# SPE_router_eth.net
KiCad netlist of a schematic drawn in Altium Designer
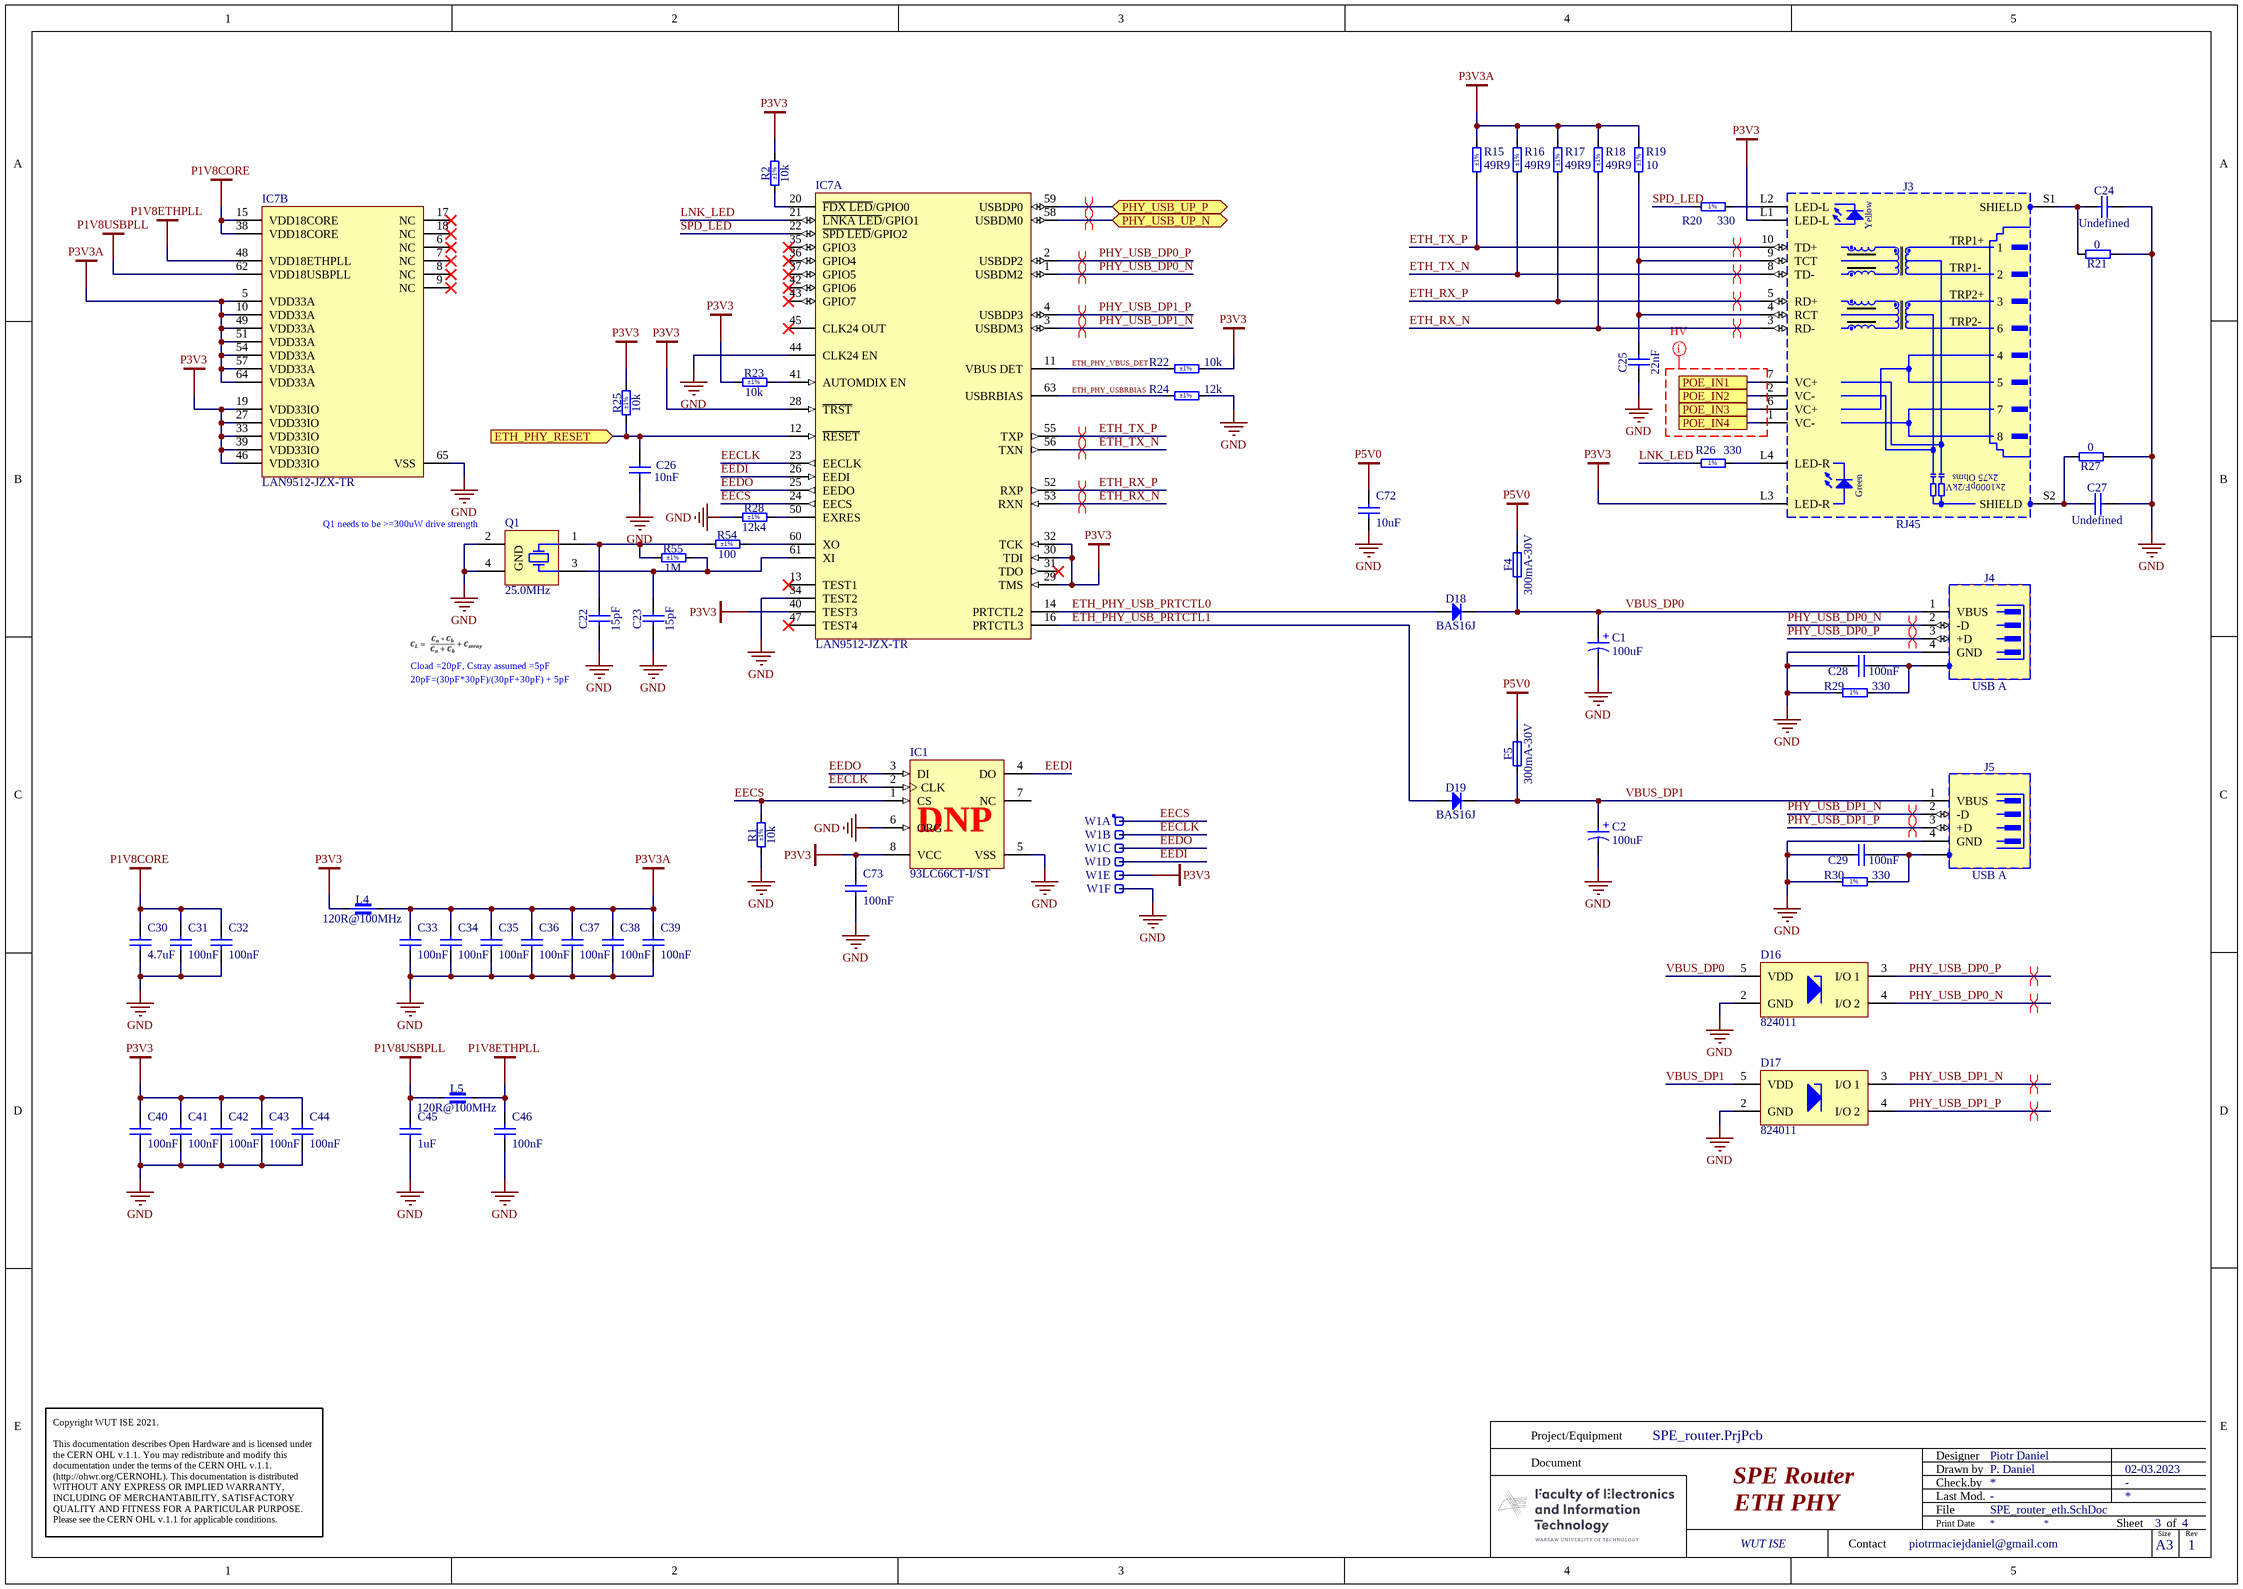
[diagram p0: SPE_router_eth.SchDoc]

(export (version "E")
  (design (tool "Eeschema 10.0.6"))
  (components
    (comp (ref "C1")
      (value "100uF")
      (footprint "WCAP-ASLU_D5H5.5")
      (description "865090142005 Electrolytic capacitor; SMD; 100uF; 6.3V; 20%; 85deg.C; 5.0x5.5")
      (fields (field (name "TOLERANCE") "20%") (field (name "MANUFACTURER") "Wurth Elektronik"))
      (libsource (lib "Altium Content Vault") (part "Capacitor_Polarized"))
    )
    (comp (ref "C2")
      (value "100uF")
      (footprint "WCAP-ASLU_D5H5.5")
      (description "865090142005 Electrolytic capacitor; SMD; 100uF; 6.3V; 20%; 85deg.C; 5.0x5.5")
      (fields (field (name "TOLERANCE") "20%") (field (name "MANUFACTURER") "Wurth Elektronik"))
      (libsource (lib "Altium Content Vault") (part "Capacitor_Polarized"))
    )
    (comp (ref "C22")
      (value "15pF")
      (footprint "CAPC1005X55N")
      (description "Non-polarised capacitor")
      (fields
        (field (name "PART NUMBER") "CC0402_15PF_50V_5%_C0G")
        (field (name "VOLTAGE") "50V")
        (field (name "AUTHOR") "CERN DEM JLC")
      )
      (libsource (lib "Capacitors") (part "Capacitor - non polarized"))
    )
    (comp (ref "C23")
      (value "15pF")
      (footprint "CAPC1005X55N")
      (description "Non-polarised capacitor")
      (fields
        (field (name "PART NUMBER") "CC0402_15PF_50V_5%_C0G")
        (field (name "VOLTAGE") "50V")
        (field (name "AUTHOR") "CERN DEM JLC")
      )
      (libsource (lib "Capacitors") (part "Capacitor - non polarized"))
    )
    (comp (ref "C24")
      (value "Undefined")
      (footprint "CAPC2012X135N")
      (description "Non-polarised capacitor")
      (fields (field (name "PART NUMBER") "CC0805_NO-VALUE") (field (name "AUTHOR") "CERN DEM JLC"))
      (libsource (lib "Capacitors") (part "Capacitor - non polarized"))
    )
    (comp (ref "C25")
      (value "22nF")
      (footprint "CAPC2012X145N")
      (description "Non-polarised capacitor")
      (fields
        (field (name "PART NUMBER") "CC0805_22NF_50V_10%_X7R_YUDEN_UMJ212BB7223KGHT")
        (field (name "VOLTAGE") "50V")
        (field (name "AUTHOR") "CERN DEM JLC")
      )
      (libsource (lib "Capacitors") (part "Capacitor - non polarized"))
    )
    (comp (ref "C26")
      (value "10nF")
      (footprint "CAPC1005X55N")
      (description "Non-polarised capacitor")
      (fields
        (field (name "PART NUMBER") "CC0402_10NF_16V_10%_X7R")
        (field (name "VOLTAGE") "16V")
        (field (name "AUTHOR") "CERN DEM JLC")
      )
      (libsource (lib "Capacitors") (part "Capacitor - non polarized"))
    )
    (comp (ref "C27")
      (value "Undefined")
      (footprint "CAPC2012X135N")
      (description "Non-polarised capacitor")
      (fields (field (name "PART NUMBER") "CC0805_NO-VALUE") (field (name "AUTHOR") "CERN DEM JLC"))
      (libsource (lib "Capacitors") (part "Capacitor - non polarized"))
    )
    (comp (ref "C28")
      (value "100nF")
      (footprint "CAPC1005X55N")
      (description "Non-polarised capacitor")
      (fields
        (field (name "PART NUMBER") "CC0402_100NF_16V_10%_X7R")
        (field (name "VOLTAGE") "16V")
        (field (name "AUTHOR") "CERN DEM JLC")
      )
      (libsource (lib "Capacitors") (part "Capacitor - non polarized"))
    )
    (comp (ref "C29")
      (value "100nF")
      (footprint "CAPC1005X55N")
      (description "Non-polarised capacitor")
      (fields
        (field (name "PART NUMBER") "CC0402_100NF_16V_10%_X7R")
        (field (name "VOLTAGE") "16V")
        (field (name "AUTHOR") "CERN DEM JLC")
      )
      (libsource (lib "Capacitors") (part "Capacitor - non polarized"))
    )
    (comp (ref "C30")
      (value "4.7uF")
      (footprint "CAPC1709X95N")
      (description "Non-polarised capacitor")
      (fields
        (field (name "PART NUMBER") "CC0603_4.7UF_16V_10%_X5R")
        (field (name "VOLTAGE") "16V")
        (field (name "AUTHOR") "CERN DEM JLC")
      )
      (libsource (lib "Capacitors") (part "Capacitor - non polarized"))
    )
    (comp (ref "C31")
      (value "100nF")
      (footprint "CAPC1005X55N")
      (description "Non-polarised capacitor")
      (fields
        (field (name "PART NUMBER") "CC0402_100NF_16V_10%_X7R")
        (field (name "VOLTAGE") "16V")
        (field (name "AUTHOR") "CERN DEM JLC")
      )
      (libsource (lib "Capacitors") (part "Capacitor - non polarized"))
    )
    (comp (ref "C32")
      (value "100nF")
      (footprint "CAPC1005X55N")
      (description "Non-polarised capacitor")
      (fields
        (field (name "PART NUMBER") "CC0402_100NF_16V_10%_X7R")
        (field (name "VOLTAGE") "16V")
        (field (name "AUTHOR") "CERN DEM JLC")
      )
      (libsource (lib "Capacitors") (part "Capacitor - non polarized"))
    )
    (comp (ref "C33")
      (value "100nF")
      (footprint "CAPC1005X55N")
      (description "Non-polarised capacitor")
      (fields
        (field (name "PART NUMBER") "CC0402_100NF_16V_10%_X7R")
        (field (name "VOLTAGE") "16V")
        (field (name "AUTHOR") "CERN DEM JLC")
      )
      (libsource (lib "Capacitors") (part "Capacitor - non polarized"))
    )
    (comp (ref "C34")
      (value "100nF")
      (footprint "CAPC1005X55N")
      (description "Non-polarised capacitor")
      (fields
        (field (name "PART NUMBER") "CC0402_100NF_16V_10%_X7R")
        (field (name "VOLTAGE") "16V")
        (field (name "AUTHOR") "CERN DEM JLC")
      )
      (libsource (lib "Capacitors") (part "Capacitor - non polarized"))
    )
    (comp (ref "C35")
      (value "100nF")
      (footprint "CAPC1005X55N")
      (description "Non-polarised capacitor")
      (fields
        (field (name "PART NUMBER") "CC0402_100NF_16V_10%_X7R")
        (field (name "VOLTAGE") "16V")
        (field (name "AUTHOR") "CERN DEM JLC")
      )
      (libsource (lib "Capacitors") (part "Capacitor - non polarized"))
    )
    (comp (ref "C36")
      (value "100nF")
      (footprint "CAPC1005X55N")
      (description "Non-polarised capacitor")
      (fields
        (field (name "PART NUMBER") "CC0402_100NF_16V_10%_X7R")
        (field (name "VOLTAGE") "16V")
        (field (name "AUTHOR") "CERN DEM JLC")
      )
      (libsource (lib "Capacitors") (part "Capacitor - non polarized"))
    )
    (comp (ref "C37")
      (value "100nF")
      (footprint "CAPC1005X55N")
      (description "Non-polarised capacitor")
      (fields
        (field (name "PART NUMBER") "CC0402_100NF_16V_10%_X7R")
        (field (name "VOLTAGE") "16V")
        (field (name "AUTHOR") "CERN DEM JLC")
      )
      (libsource (lib "Capacitors") (part "Capacitor - non polarized"))
    )
    (comp (ref "C38")
      (value "100nF")
      (footprint "CAPC1005X55N")
      (description "Non-polarised capacitor")
      (fields
        (field (name "PART NUMBER") "CC0402_100NF_16V_10%_X7R")
        (field (name "VOLTAGE") "16V")
        (field (name "AUTHOR") "CERN DEM JLC")
      )
      (libsource (lib "Capacitors") (part "Capacitor - non polarized"))
    )
    (comp (ref "C39")
      (value "100nF")
      (footprint "CAPC1005X55N")
      (description "Non-polarised capacitor")
      (fields
        (field (name "PART NUMBER") "CC0402_100NF_16V_10%_X7R")
        (field (name "VOLTAGE") "16V")
        (field (name "AUTHOR") "CERN DEM JLC")
      )
      (libsource (lib "Capacitors") (part "Capacitor - non polarized"))
    )
    (comp (ref "C40")
      (value "100nF")
      (footprint "CAPC1005X55N")
      (description "Non-polarised capacitor")
      (fields
        (field (name "PART NUMBER") "CC0402_100NF_16V_10%_X7R")
        (field (name "VOLTAGE") "16V")
        (field (name "AUTHOR") "CERN DEM JLC")
      )
      (libsource (lib "Capacitors") (part "Capacitor - non polarized"))
    )
    (comp (ref "C41")
      (value "100nF")
      (footprint "CAPC1005X55N")
      (description "Non-polarised capacitor")
      (fields
        (field (name "PART NUMBER") "CC0402_100NF_16V_10%_X7R")
        (field (name "VOLTAGE") "16V")
        (field (name "AUTHOR") "CERN DEM JLC")
      )
      (libsource (lib "Capacitors") (part "Capacitor - non polarized"))
    )
    (comp (ref "C42")
      (value "100nF")
      (footprint "CAPC1005X55N")
      (description "Non-polarised capacitor")
      (fields
        (field (name "PART NUMBER") "CC0402_100NF_16V_10%_X7R")
        (field (name "VOLTAGE") "16V")
        (field (name "AUTHOR") "CERN DEM JLC")
      )
      (libsource (lib "Capacitors") (part "Capacitor - non polarized"))
    )
    (comp (ref "C43")
      (value "100nF")
      (footprint "CAPC1005X55N")
      (description "Non-polarised capacitor")
      (fields
        (field (name "PART NUMBER") "CC0402_100NF_16V_10%_X7R")
        (field (name "VOLTAGE") "16V")
        (field (name "AUTHOR") "CERN DEM JLC")
      )
      (libsource (lib "Capacitors") (part "Capacitor - non polarized"))
    )
    (comp (ref "C44")
      (value "100nF")
      (footprint "CAPC1005X55N")
      (description "Non-polarised capacitor")
      (fields
        (field (name "PART NUMBER") "CC0402_100NF_16V_10%_X7R")
        (field (name "VOLTAGE") "16V")
        (field (name "AUTHOR") "CERN DEM JLC")
      )
      (libsource (lib "Capacitors") (part "Capacitor - non polarized"))
    )
    (comp (ref "C45")
      (value "1uF")
      (footprint "CAPC1005X55N")
      (description "Non-polarised capacitor")
      (fields
        (field (name "PART NUMBER") "CC0402_1UF_16V_10%_X5R")
        (field (name "VOLTAGE") "16V")
        (field (name "AUTHOR") "CERN DEM JLC")
      )
      (libsource (lib "Capacitors") (part "Capacitor - non polarized"))
    )
    (comp (ref "C46")
      (value "100nF")
      (footprint "CAPC1005X55N")
      (description "Non-polarised capacitor")
      (fields
        (field (name "PART NUMBER") "CC0402_100NF_16V_10%_X7R")
        (field (name "VOLTAGE") "16V")
        (field (name "AUTHOR") "CERN DEM JLC")
      )
      (libsource (lib "Capacitors") (part "Capacitor - non polarized"))
    )
    (comp (ref "C72")
      (value "10uF")
      (footprint "CAPC3216X180N")
      (description "Non-polarised capacitor")
      (fields
        (field (name "PART NUMBER") "CC1206_10UF_25V_10%_X7R")
        (field (name "VOLTAGE") "25V")
        (field (name "AUTHOR") "CERN DEM JLC")
      )
      (libsource (lib "Capacitors") (part "Capacitor - non polarized"))
    )
    (comp (ref "C73")
      (value "100nF")
      (footprint "CAPC1005X55N")
      (description "Non-polarised capacitor")
      (fields
        (field (name "PART NUMBER") "CC0402_100NF_16V_10%_X7R")
        (field (name "VOLTAGE") "16V")
        (field (name "AUTHOR") "CERN DEM JLC")
      )
      (libsource (lib "Capacitors") (part "Capacitor - non polarized"))
    )
    (comp (ref "D16")
      (value "824011")
      (footprint "WE-TVS_SOT23-5L")
      (libsource (lib "Altium Content Vault") (part "Diode_2+1 Channel_Unidirectional - 824011"))
    )
    (comp (ref "D17")
      (value "824011")
      (footprint "WE-TVS_SOT23-5L")
      (libsource (lib "Altium Content Vault") (part "Diode_2+1 Channel_Unidirectional - 824011"))
    )
    (comp (ref "D18")
      (value "BAS16J")
      (footprint "SODFL2513X80N")
      (description "Diode")
      (fields
        (field (name "VOLTAGE") "100V")
        (field (name "POWER") "250mA")
        (field (name "AUTHOR") "CERN DEM BC")
      )
      (libsource (lib "ICs And Semiconductors") (part "Diode"))
    )
    (comp (ref "D19")
      (value "BAS16J")
      (footprint "SODFL2513X80N")
      (description "Diode")
      (fields
        (field (name "VOLTAGE") "100V")
        (field (name "POWER") "250mA")
        (field (name "AUTHOR") "CERN DEM BC")
      )
      (libsource (lib "ICs And Semiconductors") (part "Diode"))
    )
    (comp (ref "F4")
      (value "300mA-30V")
      (footprint "FUSR_BOURNS_MF-MSMF_STYLE1(H110)")
      (description "Fuse")
      (fields
        (field (name "PART NUMBER") "FUSR_BOURNS_MF-MSMF030-2")
        (field (name "MANUFACTURER") "BOURNS")
        (field (name "AUTHOR") "CERN DEM JLC")
      )
      (libsource (lib "Eletro-mechanical") (part "Fuse"))
    )
    (comp (ref "F5")
      (value "300mA-30V")
      (footprint "FUSR_BOURNS_MF-MSMF_STYLE1(H110)")
      (description "Fuse")
      (fields
        (field (name "PART NUMBER") "FUSR_BOURNS_MF-MSMF030-2")
        (field (name "MANUFACTURER") "BOURNS")
        (field (name "AUTHOR") "CERN DEM JLC")
      )
      (libsource (lib "Eletro-mechanical") (part "Fuse"))
    )
    (comp (ref "IC1")
      (value "93LC66CT-I/ST")
      (footprint "TSSOP-ST8_M")
      (libsource (lib "Altium Content Vault") (part "MEM-SEEPROM-93AA46C-P-8"))
    )
    (comp (ref "IC7")
      (value "LAN9512-JZX-TR")
      (footprint "FP-LAN9512-JZX-TR-IPC_B")
      (description "USB 2.0 to 10/100 Ethernet Controllers with 2-port USB2.0 Hub, 64 QFN 9x9x0.9mm")
      (fields (field (name "MANUFACTURER") "Microchip"))
      (libsource (lib "SPE_router_lib") (part "LAN9512-JZX-TR"))
    )
    (comp (ref "J3")
      (value "RJ45")
      (footprint "ABRACON_ARJM11C7-114-BA-EW2")
      (description "MagJack 10/100BaseT, PoE+, 1X1, OG/Y, -40 to 85*C, Tab Up, RoHS")
      (fields
        (field (name "PART NUMBER") "ARJM11C7-114-BA-EW2")
        (field (name "MANUFACTURER") "Abracon")
        (field (name "AUTHOR") "GK")
      )
      (libsource (lib "SPE_router_lib") (part "CON_ETH_POE_ARJM11C7"))
    )
    (comp (ref "J4")
      (value "USB A")
      (footprint "AMPHENOL_73725-0110")
      (description "4 Pin + 1 Shield USB Receptacle")
      (fields
        (field (name "PART NUMBER") "AMPHENOL_73725-0110BLF")
        (field (name "MANUFACTURER") "AMPHENOL")
        (field (name "AUTHOR") "CERN DEM BC")
      )
      (libsource (lib "Connectors") (part "Connector USB 4 Pin + 1Shield"))
    )
    (comp (ref "J5")
      (value "USB A")
      (footprint "AMPHENOL_73725-0110")
      (description "4 Pin + 1 Shield USB Receptacle")
      (fields
        (field (name "PART NUMBER") "AMPHENOL_73725-0110BLF")
        (field (name "MANUFACTURER") "AMPHENOL")
        (field (name "AUTHOR") "CERN DEM BC")
      )
      (libsource (lib "Connectors") (part "Connector USB 4 Pin + 1Shield"))
    )
    (comp (ref "L4")
      (value "120R@100MHz")
      (footprint "INDC1608X95N")
      (fields
        (field (name "PART NUMBER") "IND0603_MURATA_BLM18PG121SN1D")
        (field (name "POWER") "2A")
        (field (name "MANUFACTURER") "MURATA")
        (field (name "AUTHOR") "CERN DEM BC")
      )
      (libsource (lib "Inductors & Transformers") (part "Ferrite Bead"))
    )
    (comp (ref "L5")
      (value "120R@100MHz")
      (footprint "INDC1608X95N")
      (fields
        (field (name "PART NUMBER") "IND0603_MURATA_BLM18PG121SN1D")
        (field (name "POWER") "2A")
        (field (name "MANUFACTURER") "MURATA")
        (field (name "AUTHOR") "CERN DEM BC")
      )
      (libsource (lib "Inductors & Transformers") (part "Ferrite Bead"))
    )
    (comp (ref "Q1")
      (value "25.0MHz")
      (footprint "XTAL_KYOCERA_CX3225SB")
      (description "Crystal 25 Mhz 12PF SMD")
      (fields
        (field (name "MANUFACTURER") "ECS International")
        (field (name "MANUFACTURER PART NUMBER") "ECS-250-12-33B-CWY-TR3")
      )
      (libsource (lib "SPE_router_lib") (part "ECS-250-12-33B-CWY-TR3"))
    )
    (comp (ref "R1")
      (value "10k")
      (footprint "RESC1005X40N")
      (description "Resistor - 1%")
      (fields
        (field (name "TOLERANCE") "±1%")
        (field (name "PART NUMBER") "R0402_10K_1%_0.0625W_100PPM")
        (field (name "POWER") "0.0625W")
        (field (name "AUTHOR") "CERN DEM JLC")
      )
      (libsource (lib "Resistors") (part "Resistor - 1%"))
    )
    (comp (ref "R2")
      (value "10k")
      (footprint "RESC1005X40N")
      (description "Resistor - 1%")
      (fields
        (field (name "TOLERANCE") "±1%")
        (field (name "PART NUMBER") "R0402_10K_1%_0.0625W_100PPM")
        (field (name "POWER") "0.0625W")
        (field (name "AUTHOR") "CERN DEM JLC")
      )
      (libsource (lib "Resistors") (part "Resistor - 1%"))
    )
    (comp (ref "R15")
      (value "49R9")
      (footprint "RESC1005X40N")
      (description "Resistor - 1%")
      (fields
        (field (name "TOLERANCE") "±1%")
        (field (name "PART NUMBER") "R0402_49R9_1%_0.0625W_100PPM")
        (field (name "POWER") "0.0625W")
        (field (name "AUTHOR") "CERN DEM JLC")
      )
      (libsource (lib "Resistors") (part "Resistor - 1%"))
    )
    (comp (ref "R16")
      (value "49R9")
      (footprint "RESC1005X40N")
      (description "Resistor - 1%")
      (fields
        (field (name "TOLERANCE") "±1%")
        (field (name "PART NUMBER") "R0402_49R9_1%_0.0625W_100PPM")
        (field (name "POWER") "0.0625W")
        (field (name "AUTHOR") "CERN DEM JLC")
      )
      (libsource (lib "Resistors") (part "Resistor - 1%"))
    )
    (comp (ref "R17")
      (value "49R9")
      (footprint "RESC1005X40N")
      (description "Resistor - 1%")
      (fields
        (field (name "TOLERANCE") "±1%")
        (field (name "PART NUMBER") "R0402_49R9_1%_0.0625W_100PPM")
        (field (name "POWER") "0.0625W")
        (field (name "AUTHOR") "CERN DEM JLC")
      )
      (libsource (lib "Resistors") (part "Resistor - 1%"))
    )
    (comp (ref "R18")
      (value "49R9")
      (footprint "RESC1005X40N")
      (description "Resistor - 1%")
      (fields
        (field (name "TOLERANCE") "±1%")
        (field (name "PART NUMBER") "R0402_49R9_1%_0.0625W_100PPM")
        (field (name "POWER") "0.0625W")
        (field (name "AUTHOR") "CERN DEM JLC")
      )
      (libsource (lib "Resistors") (part "Resistor - 1%"))
    )
    (comp (ref "R19")
      (value "10")
      (footprint "RESC1005X40N")
      (description "Resistor - 1%")
      (fields
        (field (name "TOLERANCE") "±1%")
        (field (name "PART NUMBER") "R0402_10R_1%_0.0625W_200PPM")
        (field (name "POWER") "0.0625W")
        (field (name "AUTHOR") "CERN DEM JLC")
      )
      (libsource (lib "Resistors") (part "Resistor - 1%"))
    )
    (comp (ref "R20")
      (value "330")
      (footprint "RESC1005X40N")
      (description "Resistor - 1%")
      (fields
        (field (name "PART NUMBER") "R0402_330R_1%_0.0625W_100PPM")
        (field (name "POWER") "0.0625W")
        (field (name "AUTHOR") "CERN DEM JLC")
      )
      (libsource (lib "Resistors") (part "Resistor - 1%"))
    )
    (comp (ref "R21")
      (value "0")
      (footprint "RESC1608X55N")
      (description "Resistor")
      (fields
        (field (name "PART NUMBER") "R0603_0R_JUMPER")
        (field (name "MANUFACTURER") "GENERIC")
        (field (name "AUTHOR") "CERN DEM JLC")
      )
      (libsource (lib "Resistors") (part "Resistor"))
    )
    (comp (ref "R22")
      (value "10k")
      (footprint "RESC1005X40N")
      (description "Resistor - 1%")
      (fields
        (field (name "TOLERANCE") "±1%")
        (field (name "PART NUMBER") "R0402_10K_1%_0.0625W_100PPM")
        (field (name "POWER") "0.0625W")
        (field (name "AUTHOR") "CERN DEM JLC")
      )
      (libsource (lib "Resistors") (part "Resistor - 1%"))
    )
    (comp (ref "R23")
      (value "10k")
      (footprint "RESC1005X40N")
      (description "Resistor - 1%")
      (fields
        (field (name "TOLERANCE") "±1%")
        (field (name "PART NUMBER") "R0402_10K_1%_0.0625W_100PPM")
        (field (name "POWER") "0.0625W")
        (field (name "AUTHOR") "CERN DEM JLC")
      )
      (libsource (lib "Resistors") (part "Resistor - 1%"))
    )
    (comp (ref "R24")
      (value "12k")
      (footprint "RESC1005X40N")
      (description "Resistor - 1%")
      (fields
        (field (name "TOLERANCE") "±1%")
        (field (name "PART NUMBER") "R0402_12K_1%_0.0625W_100PPM")
        (field (name "POWER") "0.0625W")
        (field (name "AUTHOR") "CERN DEM JLC")
      )
      (libsource (lib "Resistors") (part "Resistor - 1%"))
    )
    (comp (ref "R25")
      (value "10k")
      (footprint "RESC1005X40N")
      (description "Resistor - 1%")
      (fields
        (field (name "TOLERANCE") "±1%")
        (field (name "PART NUMBER") "R0402_10K_1%_0.0625W_100PPM")
        (field (name "POWER") "0.0625W")
        (field (name "AUTHOR") "CERN DEM JLC")
      )
      (libsource (lib "Resistors") (part "Resistor - 1%"))
    )
    (comp (ref "R26")
      (value "330")
      (footprint "RESC1005X40N")
      (description "Resistor - 1%")
      (fields
        (field (name "PART NUMBER") "R0402_330R_1%_0.0625W_100PPM")
        (field (name "POWER") "0.0625W")
        (field (name "AUTHOR") "CERN DEM JLC")
      )
      (libsource (lib "Resistors") (part "Resistor - 1%"))
    )
    (comp (ref "R27")
      (value "0")
      (footprint "RESC1608X55N")
      (description "Resistor")
      (fields
        (field (name "PART NUMBER") "R0603_0R_JUMPER")
        (field (name "MANUFACTURER") "GENERIC")
        (field (name "AUTHOR") "CERN DEM JLC")
      )
      (libsource (lib "Resistors") (part "Resistor"))
    )
    (comp (ref "R28")
      (value "12k4")
      (footprint "RESC1005X40N")
      (description "Resistor - 1%")
      (fields
        (field (name "TOLERANCE") "±1%")
        (field (name "PART NUMBER") "R0402_12K4_1%_0.0625W_100PPM")
        (field (name "POWER") "0.0625W")
        (field (name "AUTHOR") "CERN DEM BC")
      )
      (libsource (lib "Resistors") (part "Resistor - 1%"))
    )
    (comp (ref "R29")
      (value "330")
      (footprint "RESC1005X40N")
      (description "Resistor - 1%")
      (fields
        (field (name "PART NUMBER") "R0402_330R_1%_0.0625W_100PPM")
        (field (name "POWER") "0.0625W")
        (field (name "AUTHOR") "CERN DEM JLC")
      )
      (libsource (lib "Resistors") (part "Resistor - 1%"))
    )
    (comp (ref "R30")
      (value "330")
      (footprint "RESC1005X40N")
      (description "Resistor - 1%")
      (fields
        (field (name "PART NUMBER") "R0402_330R_1%_0.0625W_100PPM")
        (field (name "POWER") "0.0625W")
        (field (name "AUTHOR") "CERN DEM JLC")
      )
      (libsource (lib "Resistors") (part "Resistor - 1%"))
    )
    (comp (ref "R54")
      (value "100")
      (footprint "RESC1005X40N")
      (description "Resistor - 1%")
      (fields
        (field (name "PART NUMBER") "R0402_100R_1%_0.0625W_100PPM")
        (field (name "MANUFACTURER") "GENERIC")
        (field (name "TOLERANCE") "±1%")
        (field (name "AUTHOR") "CERN DEM JLC")
      )
      (libsource (lib "Resistors") (part "Resistor - 1%"))
    )
    (comp (ref "R55")
      (value "1M")
      (footprint "RESC1005X40N")
      (description "Resistor - 1%")
      (fields
        (field (name "TOLERANCE") "±1%")
        (field (name "PART NUMBER") "R0402_1M_1%_0.0625W_100PPM")
        (field (name "POWER") "0.0625W")
        (field (name "AUTHOR") "CERN DEM JLC")
      )
      (libsource (lib "Resistors") (part "Resistor - 1%"))
    )
    (comp (ref "W1")
      (value "Header 6")
      (footprint "SAMTEC_TSW-106-23-L-S")
      (description "6 Mini Wire-Wrap Contact Strip Header")
      (fields
        (field (name "PART NUMBER") "SAMTEC_TSW-106-23-L-S")
        (field (name "MANUFACTURER") "SAMTEC")
        (field (name "AUTHOR") "CERN DEM BC")
      )
      (libsource (lib "Connectors") (part "Wire-Wrap Contact x6"))
    )
  )
  (nets
    (net (code "1") (name "/EECLK") (class "Default")
      (node (ref "IC1") (pin "2") (pinfunction "CLK_2") (pintype "input"))
      (node (ref "IC7") (pin "23") (pinfunction "EECLK_23") (pintype "output"))
      (node (ref "W1") (pin "2") (pinfunction "2_2") (pintype "bidirectional"))
    )
    (net (code "2") (name "/EECS") (class "Default")
      (node (ref "IC1") (pin "1") (pinfunction "CS_1") (pintype "input"))
      (node (ref "IC7") (pin "24") (pinfunction "EECS_24") (pintype "output"))
      (node (ref "R1") (pin "2") (pinfunction "2_2") (pintype "passive"))
      (node (ref "W1") (pin "1") (pinfunction "1_1") (pintype "bidirectional"))
    )
    (net (code "3") (name "/EEDI") (class "Default")
      (node (ref "IC1") (pin "4") (pinfunction "DO_4") (pintype "tri_state"))
      (node (ref "IC7") (pin "26") (pinfunction "EEDI_26") (pintype "input"))
      (node (ref "W1") (pin "4") (pinfunction "4_4") (pintype "bidirectional"))
    )
    (net (code "4") (name "/EEDO") (class "Default")
      (node (ref "IC1") (pin "3") (pinfunction "DI_3") (pintype "input"))
      (node (ref "IC7") (pin "25") (pinfunction "EEDO_25") (pintype "output"))
      (node (ref "W1") (pin "3") (pinfunction "3_3") (pintype "bidirectional"))
    )
    (net (code "5") (name "/ETH_PHY_RESET") (class "Default")
      (node (ref "C26") (pin "2") (pinfunction "2_2") (pintype "passive"))
      (node (ref "IC7") (pin "12") (pinfunction "~{RESET}_12") (pintype "input"))
      (node (ref "R25") (pin "1") (pinfunction "1_1") (pintype "passive"))
    )
    (net (code "6") (name "/ETH_PHY_USBRBIAS") (class "Default")
      (node (ref "IC7") (pin "63") (pinfunction "USBRBIAS_63") (pintype "passive"))
      (node (ref "R24") (pin "1") (pinfunction "1_1") (pintype "passive"))
    )
    (net (code "7") (name "/ETH_PHY_USB_PRTCTL0") (class "Default")
      (node (ref "D18") (pin "2") (pinfunction "A_2") (pintype "passive"))
      (node (ref "IC7") (pin "14") (pinfunction "PRTCTL2_14") (pintype "passive"))
    )
    (net (code "8") (name "/ETH_PHY_USB_PRTCTL1") (class "Default")
      (node (ref "D19") (pin "2") (pinfunction "A_2") (pintype "passive"))
      (node (ref "IC7") (pin "16") (pinfunction "PRTCTL3_16") (pintype "passive"))
    )
    (net (code "9") (name "/ETH_PHY_VBUS_DET") (class "Default")
      (node (ref "IC7") (pin "11") (pinfunction "VBUS_DET_11") (pintype "power_in"))
      (node (ref "R22") (pin "1") (pinfunction "1_1") (pintype "passive"))
    )
    (net (code "10") (name "/ETH_RX_N") (class "Default")
      (node (ref "IC7") (pin "53") (pinfunction "RXN_53") (pintype "input"))
      (node (ref "J3") (pin "3") (pinfunction "RD-_3") (pintype "bidirectional"))
      (node (ref "R18") (pin "1") (pinfunction "1_1") (pintype "passive"))
    )
    (net (code "11") (name "/ETH_RX_P") (class "Default")
      (node (ref "IC7") (pin "52") (pinfunction "RXP_52") (pintype "output"))
      (node (ref "J3") (pin "5") (pinfunction "RD+_5") (pintype "bidirectional"))
      (node (ref "R17") (pin "1") (pinfunction "1_1") (pintype "passive"))
    )
    (net (code "12") (name "/ETH_TX_N") (class "Default")
      (node (ref "IC7") (pin "56") (pinfunction "TXN_56") (pintype "output"))
      (node (ref "J3") (pin "8") (pinfunction "TD-_8") (pintype "bidirectional"))
      (node (ref "R16") (pin "1") (pinfunction "1_1") (pintype "passive"))
    )
    (net (code "13") (name "/ETH_TX_P") (class "Default")
      (node (ref "IC7") (pin "55") (pinfunction "TXP_55") (pintype "output"))
      (node (ref "J3") (pin "10") (pinfunction "TD+_10") (pintype "bidirectional"))
      (node (ref "R15") (pin "1") (pinfunction "1_1") (pintype "passive"))
    )
    (net (code "14") (name "/LNK_LED") (class "Default")
      (node (ref "IC7") (pin "21") (pinfunction "~{LNKA_LED}/GPIO1_21") (pintype "bidirectional"))
      (node (ref "R26") (pin "1") (pinfunction "1_1") (pintype "passive"))
    )
    (net (code "15") (name "/PHY_USB_DP0_N") (class "Default")
      (node (ref "D16") (pin "4") (pinfunction "I/O_2_4") (pintype "passive"))
      (node (ref "IC7") (pin "1") (pinfunction "USBDM2_1") (pintype "bidirectional"))
      (node (ref "J4") (pin "2") (pinfunction "-D_2") (pintype "bidirectional"))
    )
    (net (code "16") (name "/PHY_USB_DP0_P") (class "Default")
      (node (ref "D16") (pin "3") (pinfunction "I/O_1_3") (pintype "passive"))
      (node (ref "IC7") (pin "2") (pinfunction "USBDP2_2") (pintype "bidirectional"))
      (node (ref "J4") (pin "3") (pinfunction "+D_3") (pintype "bidirectional"))
    )
    (net (code "17") (name "/PHY_USB_DP1_N") (class "Default")
      (node (ref "D17") (pin "3") (pinfunction "I/O_1_3") (pintype "passive"))
      (node (ref "IC7") (pin "3") (pinfunction "USBDM3_3") (pintype "bidirectional"))
      (node (ref "J5") (pin "2") (pinfunction "-D_2") (pintype "bidirectional"))
    )
    (net (code "18") (name "/PHY_USB_DP1_P") (class "Default")
      (node (ref "D17") (pin "4") (pinfunction "I/O_2_4") (pintype "passive"))
      (node (ref "IC7") (pin "4") (pinfunction "USBDP3_4") (pintype "bidirectional"))
      (node (ref "J5") (pin "3") (pinfunction "+D_3") (pintype "bidirectional"))
    )
    (net (code "19") (name "/PHY_USB_UP_N") (class "Default")
      (node (ref "IC7") (pin "58") (pinfunction "USBDM0_58") (pintype "bidirectional"))
    )
    (net (code "20") (name "/PHY_USB_UP_P") (class "Default")
      (node (ref "IC7") (pin "59") (pinfunction "USBDP0_59") (pintype "bidirectional"))
    )
    (net (code "21") (name "/POE_IN1") (class "Default")
      (node (ref "J3") (pin "7") (pinfunction "VC+_7") (pintype "passive"))
    )
    (net (code "22") (name "/POE_IN2") (class "Default")
      (node (ref "J3") (pin "2") (pinfunction "VC-_2") (pintype "passive"))
    )
    (net (code "23") (name "/POE_IN3") (class "Default")
      (node (ref "J3") (pin "6") (pinfunction "VC+_6") (pintype "passive"))
    )
    (net (code "24") (name "/POE_IN4") (class "Default")
      (node (ref "J3") (pin "1") (pinfunction "VC-_1") (pintype "passive"))
    )
    (net (code "25") (name "/SPD_LED") (class "Default")
      (node (ref "IC7") (pin "22") (pinfunction "~{SPD_LED}/GPIO2_22") (pintype "bidirectional"))
      (node (ref "R20") (pin "1") (pinfunction "1_1") (pintype "passive"))
    )
    (net (code "26") (name "/VBUS_DP0") (class "Default")
      (node (ref "C1") (pin "1") (pinfunction "P_1") (pintype "passive"))
      (node (ref "D16") (pin "5") (pinfunction "VDD_5") (pintype "passive"))
      (node (ref "D18") (pin "1") (pinfunction "C_1") (pintype "passive"))
      (node (ref "F4") (pin "1") (pinfunction "1_1") (pintype "passive"))
      (node (ref "J4") (pin "1") (pinfunction "VBUS_1") (pintype "power_in"))
    )
    (net (code "27") (name "/VBUS_DP1") (class "Default")
      (node (ref "C2") (pin "1") (pinfunction "P_1") (pintype "passive"))
      (node (ref "D17") (pin "5") (pinfunction "VDD_5") (pintype "passive"))
      (node (ref "D19") (pin "1") (pinfunction "C_1") (pintype "passive"))
      (node (ref "F5") (pin "1") (pinfunction "1_1") (pintype "passive"))
      (node (ref "J5") (pin "1") (pinfunction "VBUS_1") (pintype "power_in"))
    )
    (net (code "28") (name "GND") (class "Default")
      (node (ref "C1") (pin "2") (pinfunction "N_2") (pintype "passive"))
      (node (ref "C2") (pin "2") (pinfunction "N_2") (pintype "passive"))
      (node (ref "C22") (pin "1") (pinfunction "1_1") (pintype "passive"))
      (node (ref "C23") (pin "1") (pinfunction "1_1") (pintype "passive"))
      (node (ref "C24") (pin "2") (pinfunction "2_2") (pintype "passive"))
      (node (ref "C25") (pin "1") (pinfunction "1_1") (pintype "passive"))
      (node (ref "C26") (pin "1") (pinfunction "1_1") (pintype "passive"))
      (node (ref "C27") (pin "2") (pinfunction "2_2") (pintype "passive"))
      (node (ref "C28") (pin "1") (pinfunction "1_1") (pintype "passive"))
      (node (ref "C29") (pin "1") (pinfunction "1_1") (pintype "passive"))
      (node (ref "C30") (pin "1") (pinfunction "1_1") (pintype "passive"))
      (node (ref "C31") (pin "1") (pinfunction "1_1") (pintype "passive"))
      (node (ref "C32") (pin "1") (pinfunction "1_1") (pintype "passive"))
      (node (ref "C33") (pin "1") (pinfunction "1_1") (pintype "passive"))
      (node (ref "C34") (pin "1") (pinfunction "1_1") (pintype "passive"))
      (node (ref "C35") (pin "1") (pinfunction "1_1") (pintype "passive"))
      (node (ref "C36") (pin "1") (pinfunction "1_1") (pintype "passive"))
      (node (ref "C37") (pin "1") (pinfunction "1_1") (pintype "passive"))
      (node (ref "C38") (pin "1") (pinfunction "1_1") (pintype "passive"))
      (node (ref "C39") (pin "1") (pinfunction "1_1") (pintype "passive"))
      (node (ref "C40") (pin "1") (pinfunction "1_1") (pintype "passive"))
      (node (ref "C41") (pin "1") (pinfunction "1_1") (pintype "passive"))
      (node (ref "C42") (pin "1") (pinfunction "1_1") (pintype "passive"))
      (node (ref "C43") (pin "1") (pinfunction "1_1") (pintype "passive"))
      (node (ref "C44") (pin "1") (pinfunction "1_1") (pintype "passive"))
      (node (ref "C45") (pin "1") (pinfunction "1_1") (pintype "passive"))
      (node (ref "C46") (pin "1") (pinfunction "1_1") (pintype "passive"))
      (node (ref "C72") (pin "1") (pinfunction "1_1") (pintype "passive"))
      (node (ref "C73") (pin "1") (pinfunction "1_1") (pintype "passive"))
      (node (ref "D16") (pin "2") (pinfunction "GND_2") (pintype "passive"))
      (node (ref "D17") (pin "2") (pinfunction "GND_2") (pintype "passive"))
      (node (ref "IC1") (pin "5") (pinfunction "VSS_5") (pintype "power_in"))
      (node (ref "IC1") (pin "6") (pinfunction "ORG_6") (pintype "input"))
      (node (ref "IC7") (pin "34") (pinfunction "TEST2_34") (pintype "passive"))
      (node (ref "IC7") (pin "44") (pinfunction "CLK24_EN_44") (pintype "passive"))
      (node (ref "IC7") (pin "65") (pinfunction "VSS_65") (pintype "power_in"))
      (node (ref "J4") (pin "4") (pinfunction "GND_4") (pintype "power_in"))
      (node (ref "J5") (pin "4") (pinfunction "GND_4") (pintype "power_in"))
      (node (ref "Q1") (pin "2") (pinfunction "GND_2") (pintype "power_in"))
      (node (ref "Q1") (pin "4") (pinfunction "GND_4") (pintype "power_in"))
      (node (ref "R1") (pin "1") (pinfunction "1_1") (pintype "passive"))
      (node (ref "R21") (pin "1") (pinfunction "1_1") (pintype "passive"))
      (node (ref "R24") (pin "2") (pinfunction "2_2") (pintype "passive"))
      (node (ref "R27") (pin "1") (pinfunction "1_1") (pintype "passive"))
      (node (ref "R28") (pin "1") (pinfunction "1_1") (pintype "passive"))
      (node (ref "R29") (pin "1") (pinfunction "1_1") (pintype "passive"))
      (node (ref "R30") (pin "1") (pinfunction "1_1") (pintype "passive"))
      (node (ref "W1") (pin "6") (pinfunction "6_6") (pintype "bidirectional"))
    )
    (net (code "29") (name "Net-(C22-Pad2)") (class "Default")
      (node (ref "C22") (pin "2") (pinfunction "2_2") (pintype "passive"))
      (node (ref "Q1") (pin "1") (pinfunction "X_1") (pintype "passive"))
      (node (ref "R54") (pin "1") (pinfunction "1_1") (pintype "passive"))
      (node (ref "R55") (pin "1") (pinfunction "1_1") (pintype "passive"))
    )
    (net (code "30") (name "Net-(C24-Pad1)") (class "Default")
      (node (ref "C24") (pin "1") (pinfunction "1_1") (pintype "passive"))
      (node (ref "J3") (pin "S1") (pinfunction "SHIELD_S1") (pintype "power_in"))
      (node (ref "R21") (pin "2") (pinfunction "2_2") (pintype "passive"))
    )
    (net (code "31") (name "Net-(C27-Pad1)") (class "Default")
      (node (ref "C27") (pin "1") (pinfunction "1_1") (pintype "passive"))
      (node (ref "J3") (pin "S2") (pinfunction "SHIELD_S2") (pintype "power_in"))
      (node (ref "R27") (pin "2") (pinfunction "2_2") (pintype "passive"))
    )
    (net (code "32") (name "Net-(IC7A-AUTOMDIX_EN)") (class "Default")
      (node (ref "IC7") (pin "41") (pinfunction "AUTOMDIX_EN_41") (pintype "input"))
      (node (ref "R23") (pin "2") (pinfunction "2_2") (pintype "passive"))
    )
    (net (code "33") (name "Net-(IC7A-EXRES)") (class "Default")
      (node (ref "IC7") (pin "50") (pinfunction "EXRES_50") (pintype "passive"))
      (node (ref "R28") (pin "2") (pinfunction "2_2") (pintype "passive"))
    )
    (net (code "34") (name "Net-(IC7A-XI)") (class "Default")
      (node (ref "C23") (pin "2") (pinfunction "2_2") (pintype "passive"))
      (node (ref "IC7") (pin "61") (pinfunction "XI_61") (pintype "passive"))
      (node (ref "Q1") (pin "3") (pinfunction "X_3") (pintype "passive"))
      (node (ref "R55") (pin "2") (pinfunction "2_2") (pintype "passive"))
    )
    (net (code "35") (name "Net-(IC7A-XO)") (class "Default")
      (node (ref "IC7") (pin "60") (pinfunction "XO_60") (pintype "passive"))
      (node (ref "R54") (pin "2") (pinfunction "2_2") (pintype "passive"))
    )
    (net (code "36") (name "Net-(IC7A-~{FDX_LED}{slash}GPIO0)") (class "Default")
      (node (ref "IC7") (pin "20") (pinfunction "~{FDX_LED}/GPIO0_20") (pintype "passive"))
      (node (ref "R2") (pin "1") (pinfunction "1_1") (pintype "passive"))
    )
    (net (code "37") (name "Net-(J3-LED-L-PadL2)") (class "Default")
      (node (ref "J3") (pin "L2") (pinfunction "LED-L_L2") (pintype "passive"))
      (node (ref "R20") (pin "2") (pinfunction "2_2") (pintype "passive"))
    )
    (net (code "38") (name "Net-(J3-LED-R-PadL4)") (class "Default")
      (node (ref "J3") (pin "L4") (pinfunction "LED-R_L4") (pintype "passive"))
      (node (ref "R26") (pin "2") (pinfunction "2_2") (pintype "passive"))
    )
    (net (code "39") (name "Net-(J3-RCT)") (class "Default")
      (node (ref "C25") (pin "2") (pinfunction "2_2") (pintype "passive"))
      (node (ref "J3") (pin "4") (pinfunction "RCT_4") (pintype "bidirectional"))
      (node (ref "J3") (pin "9") (pinfunction "TCT_9") (pintype "bidirectional"))
      (node (ref "R19") (pin "1") (pinfunction "1_1") (pintype "passive"))
    )
    (net (code "40") (name "Net-(J4-SHIELD)") (class "Default")
      (node (ref "C28") (pin "2") (pinfunction "2_2") (pintype "passive"))
      (node (ref "J4") (pin "5") (pinfunction "SHIELD_5") (pintype "power_in"))
      (node (ref "R29") (pin "2") (pinfunction "2_2") (pintype "passive"))
    )
    (net (code "41") (name "Net-(J5-SHIELD)") (class "Default")
      (node (ref "C29") (pin "2") (pinfunction "2_2") (pintype "passive"))
      (node (ref "J5") (pin "5") (pinfunction "SHIELD_5") (pintype "power_in"))
      (node (ref "R30") (pin "2") (pinfunction "2_2") (pintype "passive"))
    )
    (net (code "42") (name "P1V8CORE") (class "Default")
      (node (ref "C30") (pin "2") (pinfunction "2_2") (pintype "passive"))
      (node (ref "C31") (pin "2") (pinfunction "2_2") (pintype "passive"))
      (node (ref "C32") (pin "2") (pinfunction "2_2") (pintype "passive"))
      (node (ref "IC7") (pin "15") (pinfunction "VDD18CORE_15") (pintype "power_in"))
      (node (ref "IC7") (pin "38") (pinfunction "VDD18CORE_38") (pintype "power_in"))
    )
    (net (code "43") (name "P1V8ETHPLL") (class "Default")
      (node (ref "C46") (pin "2") (pinfunction "2_2") (pintype "passive"))
      (node (ref "IC7") (pin "48") (pinfunction "VDD18ETHPLL_48") (pintype "power_in"))
      (node (ref "L5") (pin "2") (pinfunction "2_2") (pintype "passive"))
    )
    (net (code "44") (name "P1V8USBPLL") (class "Default")
      (node (ref "C45") (pin "2") (pinfunction "2_2") (pintype "passive"))
      (node (ref "IC7") (pin "62") (pinfunction "VDD18USBPLL_62") (pintype "power_in"))
      (node (ref "L5") (pin "1") (pinfunction "1_1") (pintype "passive"))
    )
    (net (code "45") (name "P3V3") (class "Default")
      (node (ref "C40") (pin "2") (pinfunction "2_2") (pintype "passive"))
      (node (ref "C41") (pin "2") (pinfunction "2_2") (pintype "passive"))
      (node (ref "C42") (pin "2") (pinfunction "2_2") (pintype "passive"))
      (node (ref "C43") (pin "2") (pinfunction "2_2") (pintype "passive"))
      (node (ref "C44") (pin "2") (pinfunction "2_2") (pintype "passive"))
      (node (ref "C73") (pin "2") (pinfunction "2_2") (pintype "passive"))
      (node (ref "IC1") (pin "8") (pinfunction "VCC_8") (pintype "power_in"))
      (node (ref "IC7") (pin "19") (pinfunction "VDD33IO_19") (pintype "power_in"))
      (node (ref "IC7") (pin "27") (pinfunction "VDD33IO_27") (pintype "power_in"))
      (node (ref "IC7") (pin "28") (pinfunction "~{TRST}_28") (pintype "input"))
      (node (ref "IC7") (pin "29") (pinfunction "TMS_29") (pintype "input"))
      (node (ref "IC7") (pin "30") (pinfunction "TDI_30") (pintype "input"))
      (node (ref "IC7") (pin "32") (pinfunction "TCK_32") (pintype "input"))
      (node (ref "IC7") (pin "33") (pinfunction "VDD33IO_33") (pintype "power_in"))
      (node (ref "IC7") (pin "39") (pinfunction "VDD33IO_39") (pintype "power_in"))
      (node (ref "IC7") (pin "40") (pinfunction "TEST3_40") (pintype "passive"))
      (node (ref "IC7") (pin "46") (pinfunction "VDD33IO_46") (pintype "power_in"))
      (node (ref "J3") (pin "L1") (pinfunction "LED-L_L1") (pintype "passive"))
      (node (ref "J3") (pin "L3") (pinfunction "LED-R_L3") (pintype "passive"))
      (node (ref "L4") (pin "1") (pinfunction "1_1") (pintype "passive"))
      (node (ref "R2") (pin "2") (pinfunction "2_2") (pintype "passive"))
      (node (ref "R22") (pin "2") (pinfunction "2_2") (pintype "passive"))
      (node (ref "R23") (pin "1") (pinfunction "1_1") (pintype "passive"))
      (node (ref "R25") (pin "2") (pinfunction "2_2") (pintype "passive"))
      (node (ref "W1") (pin "5") (pinfunction "5_5") (pintype "bidirectional"))
    )
    (net (code "46") (name "P3V3A") (class "Default")
      (node (ref "C33") (pin "2") (pinfunction "2_2") (pintype "passive"))
      (node (ref "C34") (pin "2") (pinfunction "2_2") (pintype "passive"))
      (node (ref "C35") (pin "2") (pinfunction "2_2") (pintype "passive"))
      (node (ref "C36") (pin "2") (pinfunction "2_2") (pintype "passive"))
      (node (ref "C37") (pin "2") (pinfunction "2_2") (pintype "passive"))
      (node (ref "C38") (pin "2") (pinfunction "2_2") (pintype "passive"))
      (node (ref "C39") (pin "2") (pinfunction "2_2") (pintype "passive"))
      (node (ref "IC7") (pin "10") (pinfunction "VDD33A_10") (pintype "power_in"))
      (node (ref "IC7") (pin "49") (pinfunction "VDD33A_49") (pintype "power_in"))
      (node (ref "IC7") (pin "5") (pinfunction "VDD33A_5") (pintype "power_in"))
      (node (ref "IC7") (pin "51") (pinfunction "VDD33A_51") (pintype "power_in"))
      (node (ref "IC7") (pin "54") (pinfunction "VDD33A_54") (pintype "power_in"))
      (node (ref "IC7") (pin "57") (pinfunction "VDD33A_57") (pintype "power_in"))
      (node (ref "IC7") (pin "64") (pinfunction "VDD33A_64") (pintype "power_in"))
      (node (ref "L4") (pin "2") (pinfunction "2_2") (pintype "passive"))
      (node (ref "R15") (pin "2") (pinfunction "2_2") (pintype "passive"))
      (node (ref "R16") (pin "2") (pinfunction "2_2") (pintype "passive"))
      (node (ref "R17") (pin "2") (pinfunction "2_2") (pintype "passive"))
      (node (ref "R18") (pin "2") (pinfunction "2_2") (pintype "passive"))
      (node (ref "R19") (pin "2") (pinfunction "2_2") (pintype "passive"))
    )
    (net (code "47") (name "P5V0") (class "Default")
      (node (ref "C72") (pin "2") (pinfunction "2_2") (pintype "passive"))
      (node (ref "F4") (pin "2") (pinfunction "2_2") (pintype "passive"))
      (node (ref "F5") (pin "2") (pinfunction "2_2") (pintype "passive"))
    )
    (net (code "48") (name "unconnected-(IC1-NC-Pad7)") (class "Default")
      (node (ref "IC1") (pin "7") (pinfunction "NC_7") (pintype "passive"))
    )
    (net (code "49") (name "unconnected-(IC7A-CLK24_OUT-Pad45)") (class "Default")
      (node (ref "IC7") (pin "45") (pinfunction "CLK24_OUT_45") (pintype "passive+no_connect"))
    )
    (net (code "50") (name "unconnected-(IC7A-GPIO3-Pad35)") (class "Default")
      (node (ref "IC7") (pin "35") (pinfunction "GPIO3_35") (pintype "bidirectional+no_connect"))
    )
    (net (code "51") (name "unconnected-(IC7A-GPIO4-Pad36)") (class "Default")
      (node (ref "IC7") (pin "36") (pinfunction "GPIO4_36") (pintype "bidirectional+no_connect"))
    )
    (net (code "52") (name "unconnected-(IC7A-GPIO5-Pad37)") (class "Default")
      (node (ref "IC7") (pin "37") (pinfunction "GPIO5_37") (pintype "bidirectional+no_connect"))
    )
    (net (code "53") (name "unconnected-(IC7A-GPIO6-Pad42)") (class "Default")
      (node (ref "IC7") (pin "42") (pinfunction "GPIO6_42") (pintype "bidirectional+no_connect"))
    )
    (net (code "54") (name "unconnected-(IC7A-GPIO7-Pad43)") (class "Default")
      (node (ref "IC7") (pin "43") (pinfunction "GPIO7_43") (pintype "bidirectional+no_connect"))
    )
    (net (code "55") (name "unconnected-(IC7A-TDO-Pad31)") (class "Default")
      (node (ref "IC7") (pin "31") (pinfunction "TDO_31") (pintype "output+no_connect"))
    )
    (net (code "56") (name "unconnected-(IC7A-TEST1-Pad13)") (class "Default")
      (node (ref "IC7") (pin "13") (pinfunction "TEST1_13") (pintype "passive+no_connect"))
    )
    (net (code "57") (name "unconnected-(IC7A-TEST4-Pad47)") (class "Default")
      (node (ref "IC7") (pin "47") (pinfunction "TEST4_47") (pintype "passive+no_connect"))
    )
    (net (code "58") (name "unconnected-(IC7B-NC-Pad6)") (class "Default")
      (node (ref "IC7") (pin "6") (pinfunction "NC_6") (pintype "passive+no_connect"))
    )
    (net (code "59") (name "unconnected-(IC7B-NC-Pad7)") (class "Default")
      (node (ref "IC7") (pin "7") (pinfunction "NC_7") (pintype "passive+no_connect"))
    )
    (net (code "60") (name "unconnected-(IC7B-NC-Pad8)") (class "Default")
      (node (ref "IC7") (pin "8") (pinfunction "NC_8") (pintype "passive+no_connect"))
    )
    (net (code "61") (name "unconnected-(IC7B-NC-Pad9)") (class "Default")
      (node (ref "IC7") (pin "9") (pinfunction "NC_9") (pintype "passive+no_connect"))
    )
    (net (code "62") (name "unconnected-(IC7B-NC-Pad17)") (class "Default")
      (node (ref "IC7") (pin "17") (pinfunction "NC_17") (pintype "passive+no_connect"))
    )
    (net (code "63") (name "unconnected-(IC7B-NC-Pad18)") (class "Default")
      (node (ref "IC7") (pin "18") (pinfunction "NC_18") (pintype "passive+no_connect"))
    )
  )
)
